# BrauV2_USBSwitch.net
KiCad netlist of a schematic drawn in Altium Designer
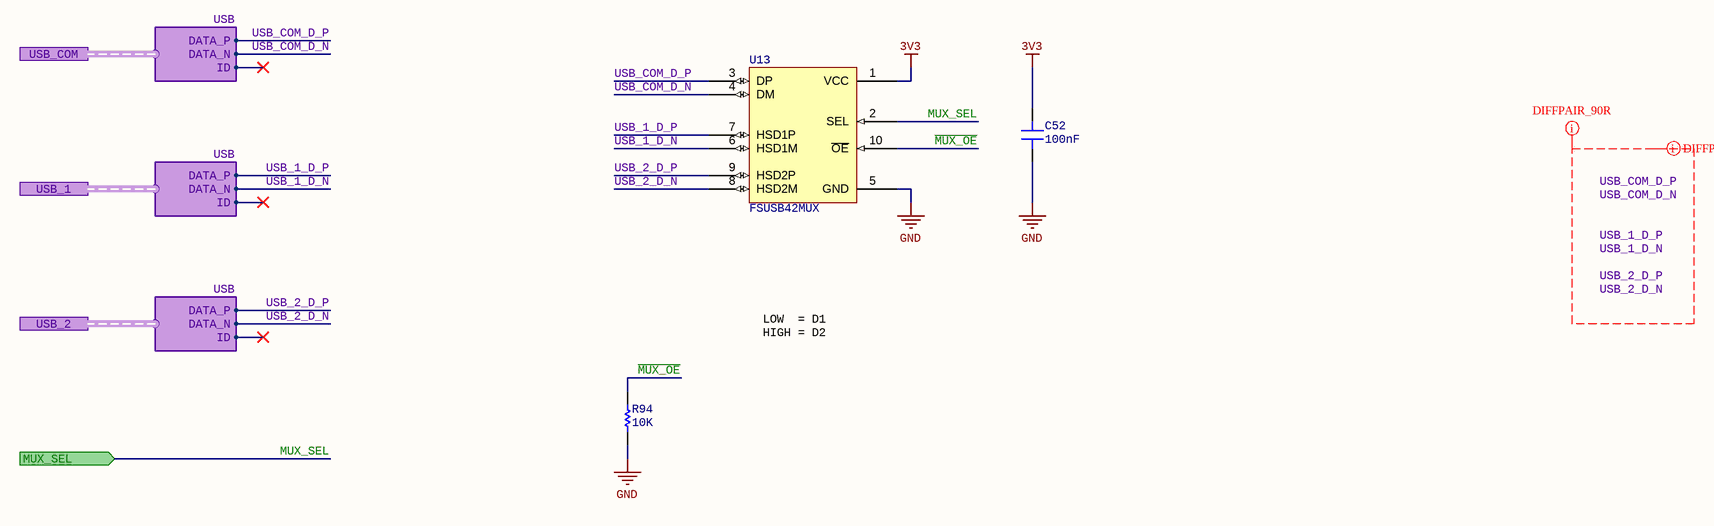
[diagram p0: BrauV2_USBSwitch.SchDoc]

(export (version "E")
  (design (tool "Eeschema 10.0.6"))
  (components
    (comp (ref "C52")
      (value "CC0402KRX5R6BB104")
      (footprint "SMD_CAP_0402(1005)_N")
      (description "100nF ±10% 10V X5R 0402 Multilayer Ceramic Capacitors MLCC - SMD/SMT RoHS")
      (fields (field (name "TOLERANCE") "10%") (field (name "CAPACITANCE") "100nF"))
      (libsource (lib "BrauV2_Capacitor") (part "100nF 0402 10V 10%"))
    )
    (comp (ref "R94")
      (value "RC0402FR-0710KL")
      (footprint "SMD_RES_0402(1005)_N")
      (description "10kΩ ±1% 1/16W ±100ppm/℃ 0402 Chip Resistor - Surface Mount RoHS")
      (fields (field (name "TOLERANCE") "1%") (field (name "RESISTANCE") "10K"))
      (libsource (lib "BrauV2_Resistor") (part "10K 0402 1% 1/16W"))
    )
    (comp (ref "U13")
      (value "FSUSB42MUX")
      (footprint "MSOP-10")
      (description "MSOP-10 USB ICs RoHS")
      (libsource (lib "BrauV2_IC") (part "FSUSB42MUX"))
    )
  )
  (nets
    (net (code "2") (name "/MUX_SEL") (class "Default")
      (node (ref "U13") (pin "2") (pinfunction "SEL_2") (pintype "input"))
    )
    (net (code "3") (name "/USB_1_D_N") (class "Default")
      (node (ref "U13") (pin "6") (pinfunction "HSD1M_6") (pintype "bidirectional"))
    )
    (net (code "4") (name "/USB_1_D_P") (class "Default")
      (node (ref "U13") (pin "7") (pinfunction "HSD1P_7") (pintype "bidirectional"))
    )
    (net (code "5") (name "/USB_2_D_N") (class "Default")
      (node (ref "U13") (pin "8") (pinfunction "HSD2M_8") (pintype "bidirectional"))
    )
    (net (code "6") (name "/USB_2_D_P") (class "Default")
      (node (ref "U13") (pin "9") (pinfunction "HSD2P_9") (pintype "bidirectional"))
    )
    (net (code "7") (name "/USB_COM_D_N") (class "Default")
      (node (ref "U13") (pin "4") (pinfunction "DM_4") (pintype "bidirectional"))
    )
    (net (code "8") (name "/USB_COM_D_P") (class "Default")
      (node (ref "U13") (pin "3") (pinfunction "DP_3") (pintype "bidirectional"))
    )
    (net (code "10") (name "/~{MUX_OE}") (class "Default")
      (node (ref "R94") (pin "2") (pinfunction "2_2") (pintype "passive"))
      (node (ref "U13") (pin "10") (pinfunction "~{OE}_10") (pintype "input"))
    )
    (net (code "11") (name "3V3") (class "Default")
      (node (ref "C52") (pin "2") (pinfunction "2_2") (pintype "passive"))
      (node (ref "U13") (pin "1") (pinfunction "VCC_1") (pintype "power_in"))
    )
    (net (code "12") (name "GND") (class "Default")
      (node (ref "C52") (pin "1") (pinfunction "1_1") (pintype "passive"))
      (node (ref "R94") (pin "1") (pinfunction "1_1") (pintype "passive"))
      (node (ref "U13") (pin "5") (pinfunction "GND_5") (pintype "power_in"))
    )
  )
)
